# SONAR_SCH.net
KiCad netlist of a schematic drawn in EAGLE
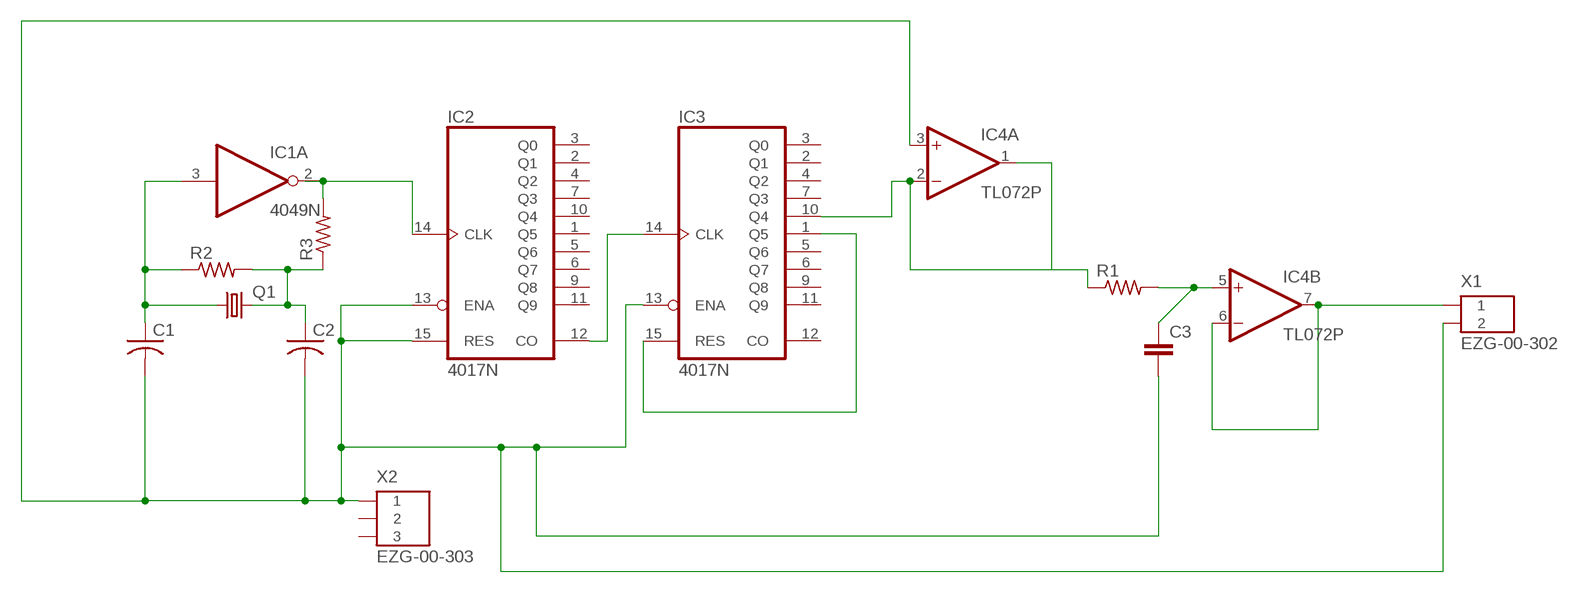
[diagram p0: schematic, sheet 1]

(export (version "E")
  (design (tool "Eeschema 10.0.6"))
  (components
    (comp (ref "C1")
      (value "C-US050-025X075")
      (footprint "eagle-import:C050-025X075")
      (libsource (lib "eagle-import") (part "C-US050-025X075"))
    )
    (comp (ref "C2")
      (value "C-US050-025X075")
      (footprint "eagle-import:C050-025X075")
      (libsource (lib "eagle-import") (part "C-US050-025X075"))
    )
    (comp (ref "C3")
      (value "C2.5/2")
      (footprint "eagle-import:C2.5-2")
      (libsource (lib "eagle-import") (part "C2.5/2"))
    )
    (comp (ref "IC1")
      (value "4049N")
      (footprint "eagle-import:DIL16")
      (libsource (lib "eagle-import") (part "4049N"))
    )
    (comp (ref "IC2")
      (value "4017N")
      (footprint "eagle-import:DIL16")
      (libsource (lib "eagle-import") (part "4017N"))
    )
    (comp (ref "IC3")
      (value "4017N")
      (footprint "eagle-import:DIL16")
      (libsource (lib "eagle-import") (part "4017N"))
    )
    (comp (ref "IC4")
      (value "TL072P")
      (footprint "eagle-import:DIL08")
      (libsource (lib "eagle-import") (part "TL072P"))
    )
    (comp (ref "Q1")
      (value "CRYSTALHC49U-V")
      (footprint "eagle-import:HC49U-V")
      (libsource (lib "eagle-import") (part "CRYSTALHC49U-V"))
    )
    (comp (ref "R1")
      (value "R-US_0207/10")
      (footprint "eagle-import:0207_10")
      (libsource (lib "eagle-import") (part "R-US_0207/10"))
    )
    (comp (ref "R2")
      (value "R-US_0207/10")
      (footprint "eagle-import:0207_10")
      (libsource (lib "eagle-import") (part "R-US_0207/10"))
    )
    (comp (ref "R3")
      (value "R-US_0207/10")
      (footprint "eagle-import:0207_10")
      (libsource (lib "eagle-import") (part "R-US_0207/10"))
    )
    (comp (ref "X1")
      (value "EZG-00-302")
      (footprint "eagle-import:EZG-00-302")
      (libsource (lib "eagle-import") (part "EZG-?-30200"))
    )
    (comp (ref "X2")
      (value "EZG-00-303")
      (footprint "eagle-import:EZG-00-303")
      (libsource (lib "eagle-import") (part "EZG-?-30300"))
    )
  )
  (nets
    (net (code "1") (name "Net-(C2-Pad1)") (class "Default")
      (node (ref "C2") (pin "1") (pinfunction "1_1") (pintype "passive"))
      (node (ref "Q1") (pin "2") (pinfunction "2_2") (pintype "passive"))
      (node (ref "R2") (pin "2") (pinfunction "2_2") (pintype "passive"))
      (node (ref "R3") (pin "1") (pinfunction "1_1") (pintype "passive"))
    )
    (net (code "2") (name "Net-(IC1A-I)") (class "Default")
      (node (ref "C1") (pin "1") (pinfunction "1_1") (pintype "passive"))
      (node (ref "IC1") (pin "3") (pinfunction "I_3") (pintype "input"))
      (node (ref "Q1") (pin "1") (pinfunction "1_1") (pintype "passive"))
      (node (ref "R2") (pin "1") (pinfunction "1_1") (pintype "passive"))
    )
    (net (code "3") (name "Net-(IC1A-O)") (class "Default")
      (node (ref "IC1") (pin "2") (pinfunction "O_2") (pintype "output"))
      (node (ref "IC2") (pin "14") (pinfunction "CLK_14") (pintype "input"))
      (node (ref "R3") (pin "2") (pinfunction "2_2") (pintype "passive"))
    )
    (net (code "4") (name "Net-(IC2A-CO)") (class "Default")
      (node (ref "IC2") (pin "12") (pinfunction "CO_12") (pintype "output"))
      (node (ref "IC3") (pin "14") (pinfunction "CLK_14") (pintype "input"))
    )
    (net (code "5") (name "Net-(IC2A-ENA)") (class "Default")
      (node (ref "C1") (pin "2") (pinfunction "2_2") (pintype "passive"))
      (node (ref "C2") (pin "2") (pinfunction "2_2") (pintype "passive"))
      (node (ref "C3") (pin "2") (pinfunction "2_2") (pintype "passive"))
      (node (ref "IC2") (pin "13") (pinfunction "ENA_13") (pintype "input"))
      (node (ref "IC2") (pin "15") (pinfunction "RES_15") (pintype "input"))
      (node (ref "IC3") (pin "13") (pinfunction "ENA_13") (pintype "input"))
      (node (ref "IC4") (pin "3") (pinfunction "+IN_3") (pintype "input"))
      (node (ref "X1") (pin "2") (pinfunction "2_2") (pintype "passive"))
      (node (ref "X2") (pin "1") (pinfunction "1_1") (pintype "passive"))
    )
    (net (code "6") (name "Net-(IC3A-Q4)") (class "Default")
      (node (ref "IC3") (pin "10") (pinfunction "Q4_10") (pintype "output"))
      (node (ref "IC4") (pin "1") (pinfunction "OUT_1") (pintype "output"))
      (node (ref "IC4") (pin "2") (pinfunction "-IN_2") (pintype "input"))
      (node (ref "R1") (pin "1") (pinfunction "1_1") (pintype "passive"))
    )
    (net (code "7") (name "Net-(IC3A-Q5)") (class "Default")
      (node (ref "IC3") (pin "1") (pinfunction "Q5_1") (pintype "output"))
      (node (ref "IC3") (pin "15") (pinfunction "RES_15") (pintype "input"))
    )
    (net (code "8") (name "Net-(IC4B-+IN)") (class "Default")
      (node (ref "C3") (pin "1") (pinfunction "1_1") (pintype "passive"))
      (node (ref "IC4") (pin "5") (pinfunction "+IN_5") (pintype "input"))
      (node (ref "R1") (pin "2") (pinfunction "2_2") (pintype "passive"))
    )
    (net (code "9") (name "Net-(IC4B--IN)") (class "Default")
      (node (ref "IC4") (pin "6") (pinfunction "-IN_6") (pintype "input"))
      (node (ref "IC4") (pin "7") (pinfunction "OUT_7") (pintype "output"))
      (node (ref "X1") (pin "1") (pinfunction "1_1") (pintype "passive"))
    )
    (net (code "10") (name "unconnected-(IC2A-Q0-Pad3)") (class "Default")
      (node (ref "IC2") (pin "3") (pinfunction "Q0_3") (pintype "output"))
    )
    (net (code "11") (name "unconnected-(IC2A-Q1-Pad2)") (class "Default")
      (node (ref "IC2") (pin "2") (pinfunction "Q1_2") (pintype "output"))
    )
    (net (code "12") (name "unconnected-(IC2A-Q2-Pad4)") (class "Default")
      (node (ref "IC2") (pin "4") (pinfunction "Q2_4") (pintype "output"))
    )
    (net (code "13") (name "unconnected-(IC2A-Q3-Pad7)") (class "Default")
      (node (ref "IC2") (pin "7") (pinfunction "Q3_7") (pintype "output"))
    )
    (net (code "14") (name "unconnected-(IC2A-Q4-Pad10)") (class "Default")
      (node (ref "IC2") (pin "10") (pinfunction "Q4_10") (pintype "output"))
    )
    (net (code "15") (name "unconnected-(IC2A-Q5-Pad1)") (class "Default")
      (node (ref "IC2") (pin "1") (pinfunction "Q5_1") (pintype "output"))
    )
    (net (code "16") (name "unconnected-(IC2A-Q6-Pad5)") (class "Default")
      (node (ref "IC2") (pin "5") (pinfunction "Q6_5") (pintype "output"))
    )
    (net (code "17") (name "unconnected-(IC2A-Q7-Pad6)") (class "Default")
      (node (ref "IC2") (pin "6") (pinfunction "Q7_6") (pintype "output"))
    )
    (net (code "18") (name "unconnected-(IC2A-Q8-Pad9)") (class "Default")
      (node (ref "IC2") (pin "9") (pinfunction "Q8_9") (pintype "output"))
    )
    (net (code "19") (name "unconnected-(IC2A-Q9-Pad11)") (class "Default")
      (node (ref "IC2") (pin "11") (pinfunction "Q9_11") (pintype "output"))
    )
    (net (code "20") (name "unconnected-(IC3A-CO-Pad12)") (class "Default")
      (node (ref "IC3") (pin "12") (pinfunction "CO_12") (pintype "output"))
    )
    (net (code "21") (name "unconnected-(IC3A-Q0-Pad3)") (class "Default")
      (node (ref "IC3") (pin "3") (pinfunction "Q0_3") (pintype "output"))
    )
    (net (code "22") (name "unconnected-(IC3A-Q1-Pad2)") (class "Default")
      (node (ref "IC3") (pin "2") (pinfunction "Q1_2") (pintype "output"))
    )
    (net (code "23") (name "unconnected-(IC3A-Q2-Pad4)") (class "Default")
      (node (ref "IC3") (pin "4") (pinfunction "Q2_4") (pintype "output"))
    )
    (net (code "24") (name "unconnected-(IC3A-Q3-Pad7)") (class "Default")
      (node (ref "IC3") (pin "7") (pinfunction "Q3_7") (pintype "output"))
    )
    (net (code "25") (name "unconnected-(IC3A-Q6-Pad5)") (class "Default")
      (node (ref "IC3") (pin "5") (pinfunction "Q6_5") (pintype "output"))
    )
    (net (code "26") (name "unconnected-(IC3A-Q7-Pad6)") (class "Default")
      (node (ref "IC3") (pin "6") (pinfunction "Q7_6") (pintype "output"))
    )
    (net (code "27") (name "unconnected-(IC3A-Q8-Pad9)") (class "Default")
      (node (ref "IC3") (pin "9") (pinfunction "Q8_9") (pintype "output"))
    )
    (net (code "28") (name "unconnected-(IC3A-Q9-Pad11)") (class "Default")
      (node (ref "IC3") (pin "11") (pinfunction "Q9_11") (pintype "output"))
    )
    (net (code "29") (name "unconnected-(X2-Pad2)") (class "Default")
      (node (ref "X2") (pin "2") (pinfunction "2_2") (pintype "passive"))
    )
    (net (code "30") (name "unconnected-(X2-Pad3)") (class "Default")
      (node (ref "X2") (pin "3") (pinfunction "3_3") (pintype "passive"))
    )
  )
)
